# ESP32_chip.net
KiCad netlist of a schematic drawn in Altium Designer
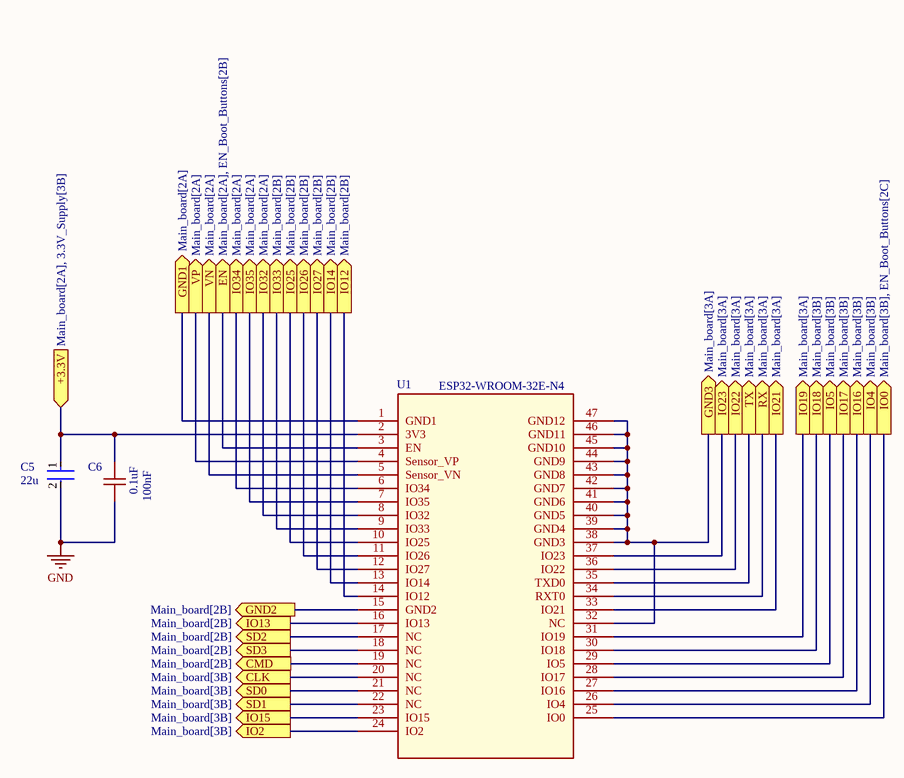
[diagram p0: ESP32_chip.SchDoc]

(export (version "E")
  (design (tool "Eeschema 10.0.6"))
  (components
    (comp (ref "C5")
      (value "22u")
      (footprint "FP-GRM21B-0_15-IPC_A")
      (description "0805 22 uF 10 V ±20% Tolerance X5R SMT Multilayer Ceramic Capacitor")
      (fields
        (field (name "MANUFACTURER") "Murata")
        (field (name "MANUFACTURER PART NUMBER") "GRM21BR61A226ME51L")
      )
      (libsource (lib "ESP32") (part "GRM21BR61A226ME51L"))
    )
    (comp (ref "C6")
      (value "100nF")
      (footprint "CAPC2013X140X45ML15T25")
      (description "Ceramic Capacitor, Ceramic, 25V, 10% +Tol, 10% -Tol, X7R, 15% TC, 0.1uF, Surface Mount, 0805")
      (fields
        (field (name "MANUFACTURER") "Murata")
        (field (name "MANUFACTURER PART NUMBER") "GCM21BR71E104KA37L")
      )
      (libsource (lib "ESP32") (part "GCM21BR71E104KA37L"))
    )
    (comp (ref "U1")
      (value "ESP32-WROOM-32E-N4")
      (footprint "ESP32­WROOM­32E_EXP")
      (description "WLAN+BT Module 2412MHz to 2484MHz 47-Pin SMD Module")
      (fields (field (name "MANUFACTURER") "Espressif Systems"))
      (libsource (lib "ESP32") (part "ESP32-WROOM-32E-N4"))
    )
  )
  (nets
    (net (code "1") (name "/+3.3V") (class "Default")
      (node (ref "C5") (pin "1") (pinfunction "1_1") (pintype "passive"))
      (node (ref "C6") (pin "2") (pinfunction "2_2") (pintype "passive"))
      (node (ref "U1") (pin "2") (pinfunction "3V3_2") (pintype "passive"))
    )
    (net (code "2") (name "/CLK") (class "Default")
      (node (ref "U1") (pin "20") (pinfunction "NC_20") (pintype "passive"))
    )
    (net (code "3") (name "/CMD") (class "Default")
      (node (ref "U1") (pin "19") (pinfunction "NC_19") (pintype "passive"))
    )
    (net (code "4") (name "/EN") (class "Default")
      (node (ref "U1") (pin "3") (pinfunction "EN_3") (pintype "passive"))
    )
    (net (code "5") (name "/GND1") (class "Default")
      (node (ref "U1") (pin "1") (pinfunction "GND1_1") (pintype "passive"))
    )
    (net (code "6") (name "/GND2") (class "Default")
      (node (ref "U1") (pin "15") (pinfunction "GND2_15") (pintype "passive"))
    )
    (net (code "7") (name "/GND3") (class "Default")
      (node (ref "U1") (pin "32") (pinfunction "NC_32") (pintype "passive"))
      (node (ref "U1") (pin "38") (pinfunction "GND3_38") (pintype "passive"))
      (node (ref "U1") (pin "39") (pinfunction "GND4_39") (pintype "passive"))
      (node (ref "U1") (pin "40") (pinfunction "GND5_40") (pintype "passive"))
      (node (ref "U1") (pin "41") (pinfunction "GND6_41") (pintype "passive"))
      (node (ref "U1") (pin "42") (pinfunction "GND7_42") (pintype "passive"))
      (node (ref "U1") (pin "43") (pinfunction "GND8_43") (pintype "passive"))
      (node (ref "U1") (pin "44") (pinfunction "GND9_44") (pintype "passive"))
      (node (ref "U1") (pin "45") (pinfunction "GND10_45") (pintype "passive"))
      (node (ref "U1") (pin "46") (pinfunction "GND11_46") (pintype "passive"))
      (node (ref "U1") (pin "47") (pinfunction "GND12_47") (pintype "passive"))
    )
    (net (code "8") (name "/IO0") (class "Default")
      (node (ref "U1") (pin "25") (pinfunction "IO0_25") (pintype "passive"))
    )
    (net (code "9") (name "/IO2") (class "Default")
      (node (ref "U1") (pin "24") (pinfunction "IO2_24") (pintype "passive"))
    )
    (net (code "10") (name "/IO4") (class "Default")
      (node (ref "U1") (pin "26") (pinfunction "IO4_26") (pintype "passive"))
    )
    (net (code "11") (name "/IO5") (class "Default")
      (node (ref "U1") (pin "29") (pinfunction "IO5_29") (pintype "passive"))
    )
    (net (code "12") (name "/IO12") (class "Default")
      (node (ref "U1") (pin "14") (pinfunction "IO12_14") (pintype "passive"))
    )
    (net (code "13") (name "/IO13") (class "Default")
      (node (ref "U1") (pin "16") (pinfunction "IO13_16") (pintype "passive"))
    )
    (net (code "14") (name "/IO14") (class "Default")
      (node (ref "U1") (pin "13") (pinfunction "IO14_13") (pintype "passive"))
    )
    (net (code "15") (name "/IO15") (class "Default")
      (node (ref "U1") (pin "23") (pinfunction "IO15_23") (pintype "passive"))
    )
    (net (code "16") (name "/IO16") (class "Default")
      (node (ref "U1") (pin "27") (pinfunction "IO16_27") (pintype "passive"))
    )
    (net (code "17") (name "/IO17") (class "Default")
      (node (ref "U1") (pin "28") (pinfunction "IO17_28") (pintype "passive"))
    )
    (net (code "18") (name "/IO18") (class "Default")
      (node (ref "U1") (pin "30") (pinfunction "IO18_30") (pintype "passive"))
    )
    (net (code "19") (name "/IO19") (class "Default")
      (node (ref "U1") (pin "31") (pinfunction "IO19_31") (pintype "passive"))
    )
    (net (code "20") (name "/IO21") (class "Default")
      (node (ref "U1") (pin "33") (pinfunction "IO21_33") (pintype "passive"))
    )
    (net (code "21") (name "/IO22") (class "Default")
      (node (ref "U1") (pin "36") (pinfunction "IO22_36") (pintype "passive"))
    )
    (net (code "22") (name "/IO23") (class "Default")
      (node (ref "U1") (pin "37") (pinfunction "IO23_37") (pintype "passive"))
    )
    (net (code "23") (name "/IO25") (class "Default")
      (node (ref "U1") (pin "10") (pinfunction "IO25_10") (pintype "passive"))
    )
    (net (code "24") (name "/IO26") (class "Default")
      (node (ref "U1") (pin "11") (pinfunction "IO26_11") (pintype "passive"))
    )
    (net (code "25") (name "/IO27") (class "Default")
      (node (ref "U1") (pin "12") (pinfunction "IO27_12") (pintype "passive"))
    )
    (net (code "26") (name "/IO32") (class "Default")
      (node (ref "U1") (pin "8") (pinfunction "IO32_8") (pintype "passive"))
    )
    (net (code "27") (name "/IO33") (class "Default")
      (node (ref "U1") (pin "9") (pinfunction "IO33_9") (pintype "passive"))
    )
    (net (code "28") (name "/IO34") (class "Default")
      (node (ref "U1") (pin "6") (pinfunction "IO34_6") (pintype "passive"))
    )
    (net (code "29") (name "/IO35") (class "Default")
      (node (ref "U1") (pin "7") (pinfunction "IO35_7") (pintype "passive"))
    )
    (net (code "30") (name "/RX") (class "Default")
      (node (ref "U1") (pin "34") (pinfunction "RXT0_34") (pintype "passive"))
    )
    (net (code "31") (name "/SD0") (class "Default")
      (node (ref "U1") (pin "21") (pinfunction "NC_21") (pintype "passive"))
    )
    (net (code "32") (name "/SD1") (class "Default")
      (node (ref "U1") (pin "22") (pinfunction "NC_22") (pintype "passive"))
    )
    (net (code "33") (name "/SD2") (class "Default")
      (node (ref "U1") (pin "17") (pinfunction "NC_17") (pintype "passive"))
    )
    (net (code "34") (name "/SD3") (class "Default")
      (node (ref "U1") (pin "18") (pinfunction "NC_18") (pintype "passive"))
    )
    (net (code "35") (name "/TX") (class "Default")
      (node (ref "U1") (pin "35") (pinfunction "TXD0_35") (pintype "passive"))
    )
    (net (code "36") (name "/VN") (class "Default")
      (node (ref "U1") (pin "5") (pinfunction "Sensor_VN_5") (pintype "passive"))
    )
    (net (code "37") (name "/VP") (class "Default")
      (node (ref "U1") (pin "4") (pinfunction "Sensor_VP_4") (pintype "passive"))
    )
    (net (code "38") (name "GND") (class "Default")
      (node (ref "C5") (pin "2") (pinfunction "2_2") (pintype "passive"))
      (node (ref "C6") (pin "1") (pinfunction "1_1") (pintype "passive"))
    )
  )
)
